# PLWD_USB.net
KiCad netlist of a schematic drawn in Altium Designer
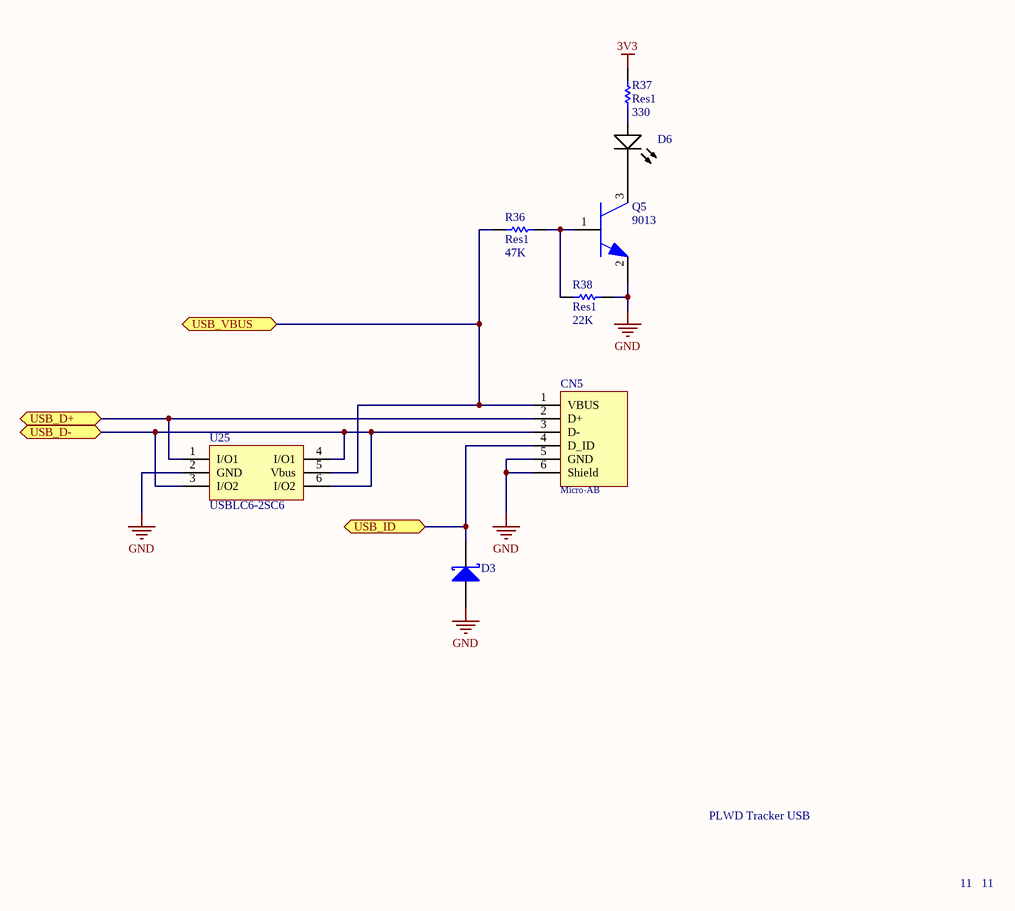
[diagram p0: PLWD_USB.SchDoc]

(export (version "E")
  (design (tool "Eeschema 10.0.6"))
  (components
    (comp (ref "CN5")
      (value "Micro-AB")
      (description "Conn Micro USB 2.0 Type AB RCP 5 POS 0.65mm Solder RA SMD 5 Terminal 1 Port Micro-USB T/R")
      (fields (field (name "MANUFACTURER") "Molex") (field (name "MANUFACTURER PART NUMBER") "0475891001"))
      (libsource (lib "PLWD_PartLib") (part "USB Micro-AB 0475891001"))
    )
    (comp (ref "D3")
      (value "D Schottky")
      (footprint "SMB")
      (description "Schottky Diode")
      (fields (field (name "PUBLISHER") "Altium Limited"))
      (libsource (lib "Miscellaneous Devices") (part "D Schottky"))
    )
    (comp (ref "D6")
      (value "16-219A/T2D-AR2T1QY/3T")
      (footprint "EVRL-0402-2_V")
      (description "Chip LED, White, 5 V, 10 mA, 30 mW, -40 to 85 degC, 2-Pin SMD (0402), RoHS, Tape and Reel")
      (fields (field (name "POWER") "30mW") (field (name "MANUFACTURER") "Everlight Electronics"))
      (libsource (lib "Carleton University") (part "LED-WHITE-AK-2"))
    )
    (comp (ref "Q5") (value "9013") (libsource (lib "PLWD_PartLib") (part "MMBT9013")))
    (comp (ref "R36")
      (value "Res1")
      (footprint "AXIAL-0.3")
      (description "Resistor")
      (fields (field (name "ALTIUM_VALUE") "47K") (field (name "PUBLISHER") "Altium Limited"))
      (libsource (lib "Miscellaneous Devices") (part "Res1"))
    )
    (comp (ref "R37")
      (value "Res1")
      (footprint "AXIAL-0.3")
      (description "Resistor")
      (fields (field (name "ALTIUM_VALUE") "330") (field (name "PUBLISHER") "Altium Limited"))
      (libsource (lib "Miscellaneous Devices") (part "Res1"))
    )
    (comp (ref "R38")
      (value "Res1")
      (footprint "AXIAL-0.3")
      (description "Resistor")
      (fields (field (name "ALTIUM_VALUE") "22K") (field (name "PUBLISHER") "Altium Limited"))
      (libsource (lib "Miscellaneous Devices") (part "Res1"))
    )
    (comp (ref "U25")
      (value "USBLC6-2SC6")
      (description "USBLC6 Series 2 Line 6 V Uni / Bi-Directional ESD Protection - SOT-23-6")
      (fields (field (name "MANUFACTURER") "STMicroelectronics"))
      (libsource (lib "PLWD_PartLib") (part "USBLC6-2SC6"))
    )
  )
  (nets
    (net (code "1") (name "/USB_D+") (class "Default")
      (node (ref "CN5") (pin "2") (pinfunction "D+_2") (pintype "passive"))
      (node (ref "U25") (pin "1") (pinfunction "I/O1_1") (pintype "passive"))
    )
    (net (code "2") (name "/USB_D-") (class "Default")
      (node (ref "CN5") (pin "3") (pinfunction "D-_3") (pintype "passive"))
      (node (ref "U25") (pin "3") (pinfunction "I/O2_3") (pintype "passive"))
      (node (ref "U25") (pin "4") (pinfunction "I/O1_4") (pintype "passive"))
      (node (ref "U25") (pin "6") (pinfunction "I/O2_6") (pintype "passive"))
    )
    (net (code "3") (name "/USB_ID") (class "Default")
      (node (ref "CN5") (pin "4") (pinfunction "D_ID_4") (pintype "passive"))
      (node (ref "D3") (pin "2") (pinfunction "K_2") (pintype "passive"))
    )
    (net (code "4") (name "/USB_VBUS") (class "Default")
      (node (ref "CN5") (pin "1") (pinfunction "VBUS_1") (pintype "passive"))
      (node (ref "R36") (pin "1") (pinfunction "1_1") (pintype "passive"))
      (node (ref "U25") (pin "5") (pinfunction "Vbus_5") (pintype "passive"))
    )
    (net (code "5") (name "3V3") (class "Default")
      (node (ref "R37") (pin "2") (pinfunction "2_2") (pintype "passive"))
    )
    (net (code "6") (name "GND") (class "Default")
      (node (ref "CN5") (pin "5") (pinfunction "GND_5") (pintype "passive"))
      (node (ref "CN5") (pin "6") (pinfunction "Shield_6") (pintype "passive"))
      (node (ref "D3") (pin "1") (pinfunction "A_1") (pintype "passive"))
      (node (ref "Q5") (pin "2") (pintype "passive"))
      (node (ref "R38") (pin "2") (pinfunction "2_2") (pintype "passive"))
      (node (ref "U25") (pin "2") (pinfunction "GND_2") (pintype "passive"))
    )
    (net (code "7") (name "Net-(D6-A)") (class "Default")
      (node (ref "D6") (pin "1") (pinfunction "A_1") (pintype "passive"))
      (node (ref "R37") (pin "1") (pinfunction "1_1") (pintype "passive"))
    )
    (net (code "8") (name "Net-(D6-K)") (class "Default")
      (node (ref "D6") (pin "2") (pinfunction "K_2") (pintype "passive"))
      (node (ref "Q5") (pin "3") (pintype "passive"))
    )
    (net (code "9") (name "Net-(Q5-Pad1)") (class "Default")
      (node (ref "Q5") (pin "1") (pintype "passive"))
      (node (ref "R36") (pin "2") (pinfunction "2_2") (pintype "passive"))
      (node (ref "R38") (pin "1") (pinfunction "1_1") (pintype "passive"))
    )
  )
)
